# v010_connector_schematics.net
KiCad netlist of a schematic drawn in Altium Designer
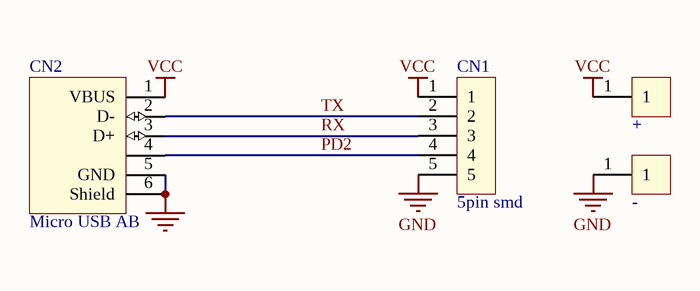
[diagram p0: v010 connector schematics.SchDoc]

(export (version "E")
  (design (tool "Eeschema 10.0.6"))
  (components
    (comp (ref "+")
      (value "No component mounted")
      (footprint "SU01LS")
      (libsource (lib "*") (part "1pin smd"))
    )
    (comp (ref "-")
      (value "No component mounted")
      (footprint "SU01LS")
      (libsource (lib "*") (part "1pin smd"))
    )
    (comp (ref "CN1")
      (value "5pin smd")
      (footprint "SU05LSR - 1MM")
      (description "No component mounted")
      (libsource (lib "v4lib") (part "5pin smd"))
    )
    (comp (ref "CN2")
      (value "Micro USB AB")
      (footprint "Micro USB Receptacle smaller")
      (description "Connector Receptacle Micro USB AB SMD Reverse Angle")
      (fields
        (field (name "DIGI-KEY PART NUMBER") "H11635CT-ND")
        (field (name "MANUFACTURER") "Hirose Electric")
      )
      (libsource (lib "v4lib") (part "micro usb"))
    )
  )
  (nets
    (net (code "1") (name "/PD2") (class "Default")
      (node (ref "CN1") (pin "4") (pinfunction "4_4") (pintype "passive"))
      (node (ref "CN2") (pin "4") (pintype "passive"))
    )
    (net (code "2") (name "/RX") (class "Default")
      (node (ref "CN1") (pin "3") (pinfunction "3_3") (pintype "passive"))
      (node (ref "CN2") (pin "3") (pinfunction "D+_3") (pintype "bidirectional"))
    )
    (net (code "3") (name "/TX") (class "Default")
      (node (ref "CN1") (pin "2") (pinfunction "2_2") (pintype "passive"))
      (node (ref "CN2") (pin "2") (pinfunction "D-_2") (pintype "bidirectional"))
    )
    (net (code "4") (name "GND") (class "Default")
      (node (ref "-") (pin "1") (pinfunction "1_1") (pintype "passive"))
      (node (ref "CN1") (pin "5") (pinfunction "5_5") (pintype "passive"))
      (node (ref "CN2") (pin "5") (pinfunction "GND_5") (pintype "passive"))
      (node (ref "CN2") (pin "6") (pinfunction "Shield_6") (pintype "passive"))
    )
    (net (code "5") (name "VCC") (class "Default")
      (node (ref "+") (pin "1") (pinfunction "1_1") (pintype "passive"))
      (node (ref "CN1") (pin "1") (pinfunction "1_1") (pintype "passive"))
      (node (ref "CN2") (pin "1") (pinfunction "VBUS_1") (pintype "power_in"))
    )
  )
)
